# Four_Track_R1.net
KiCad netlist of a schematic drawn in EAGLE
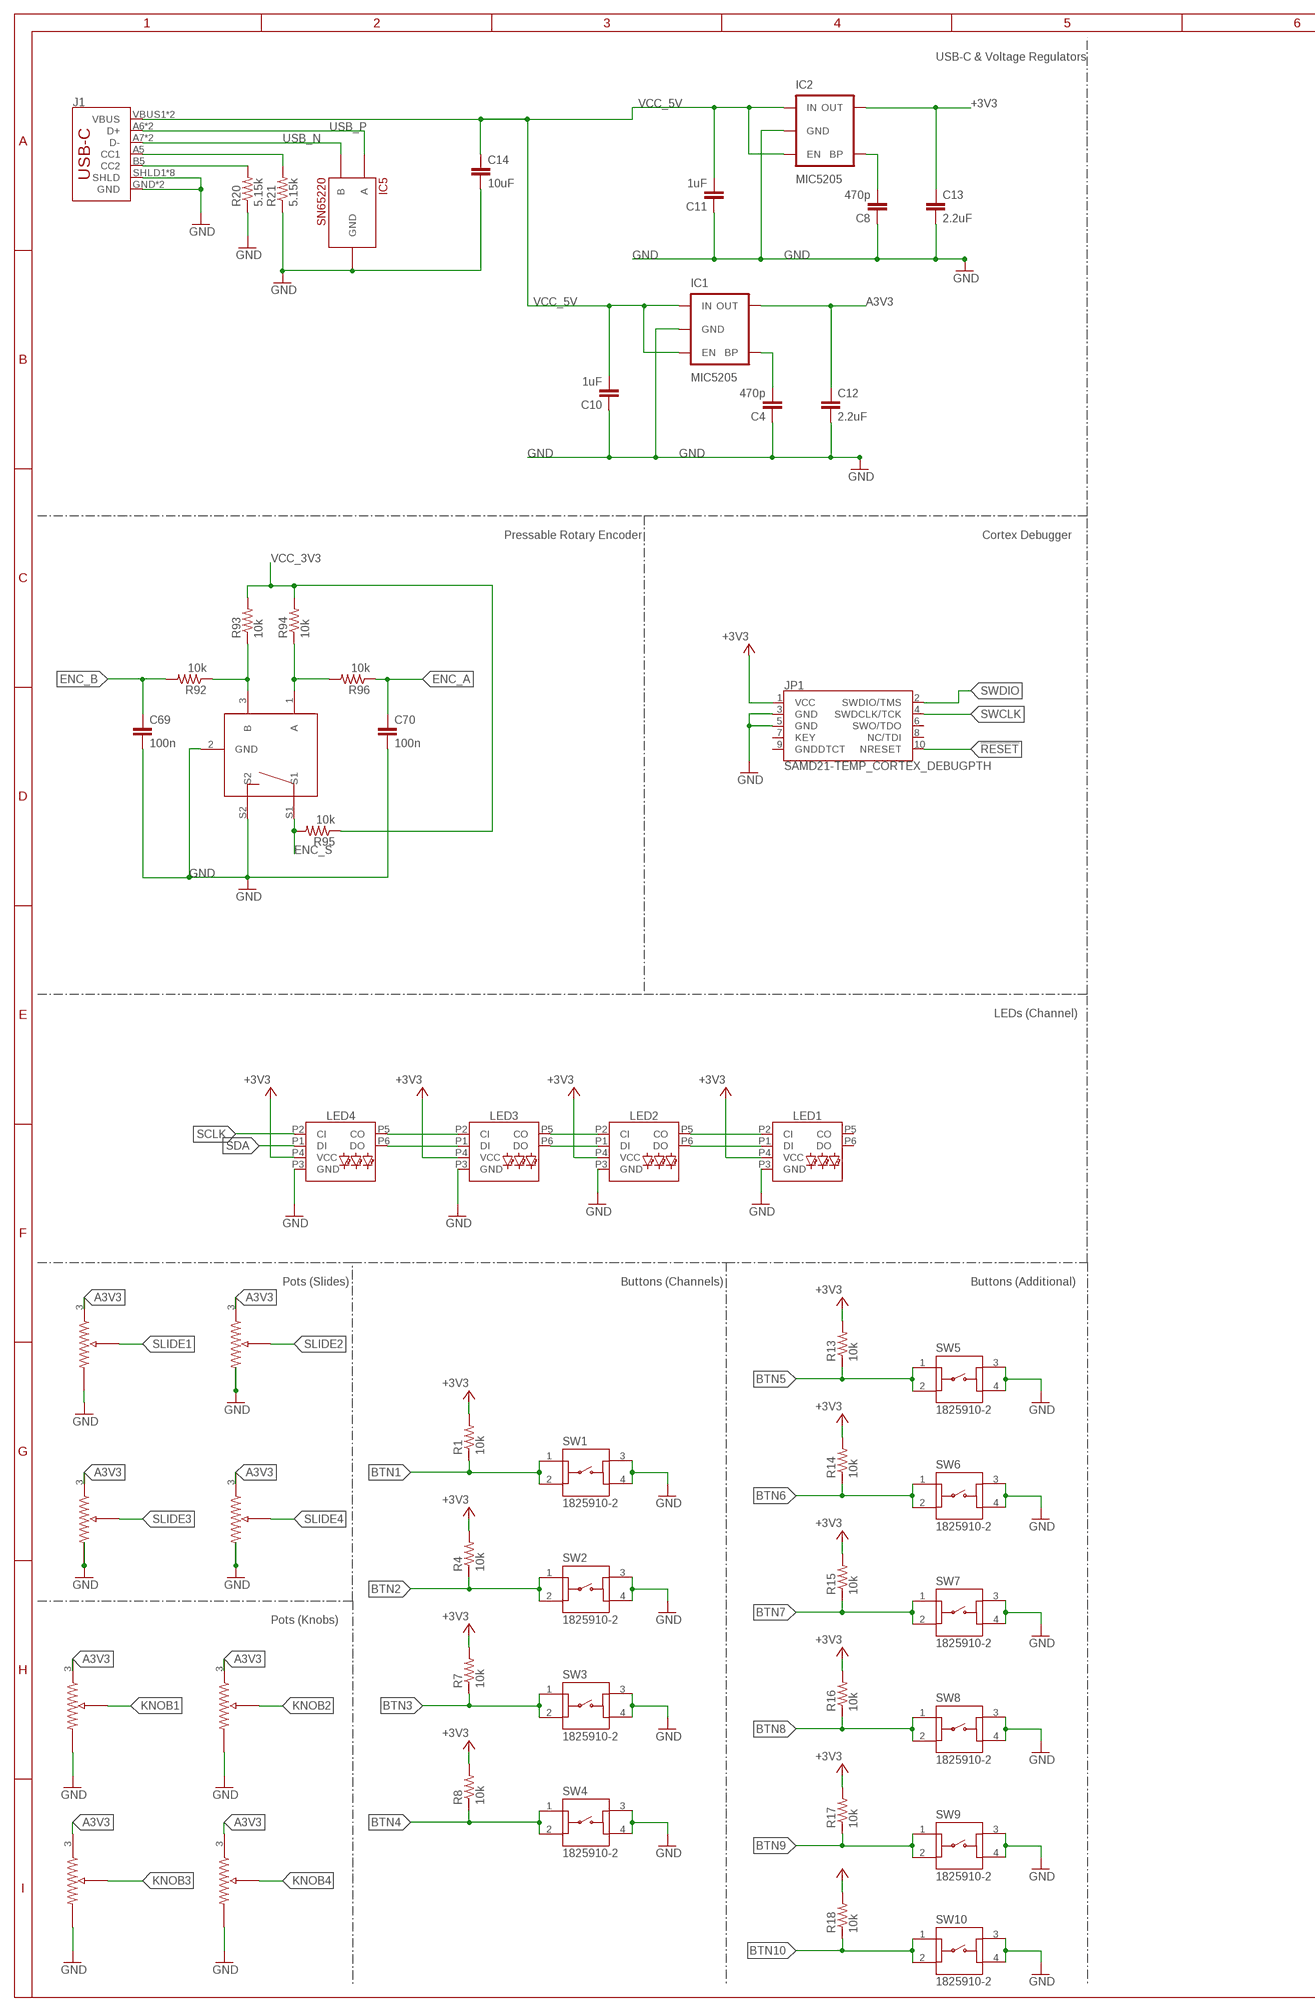
[diagram p0: schematic, sheet 1, part 1 of 2]
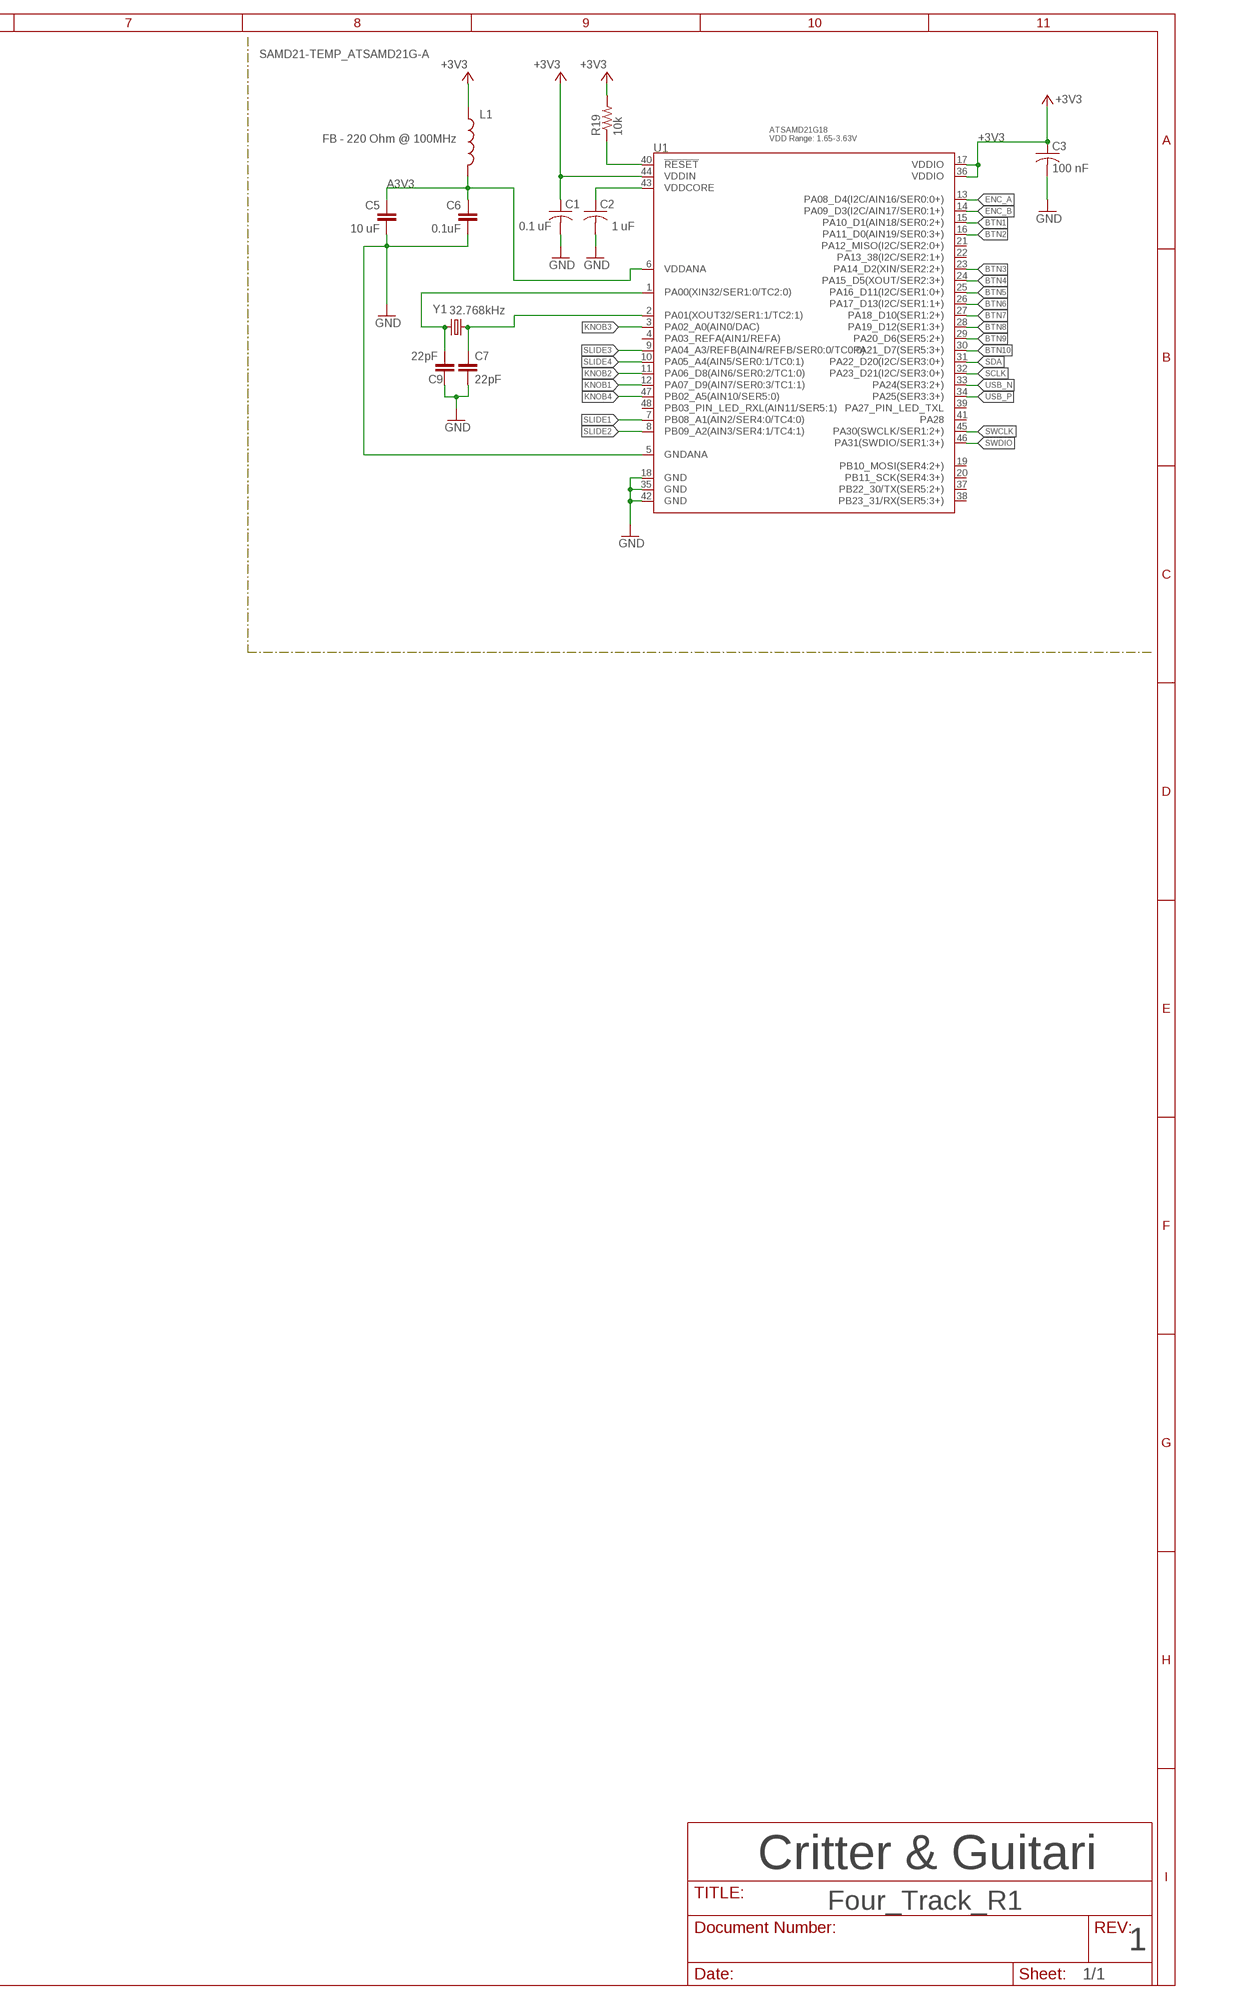
[diagram p1: schematic, sheet 1, part 2 of 2]

(export (version "E")
  (design (tool "Eeschema 10.0.6"))
  (components
    (comp (ref "C1")
      (value "0.1 uF")
      (footprint "eagle-import:C0603")
      (libsource (lib "eagle-import") (part "C-USC0603"))
    )
    (comp (ref "C2")
      (value "1 uF")
      (footprint "eagle-import:C0603")
      (libsource (lib "eagle-import") (part "C-USC0603"))
    )
    (comp (ref "C3")
      (value "100 nF")
      (footprint "eagle-import:C0603")
      (libsource (lib "eagle-import") (part "C-USC0603"))
    )
    (comp (ref "C4")
      (value "470p")
      (footprint "eagle-import:0603-CAP")
      (libsource (lib "eagle-import") (part "CAP0603-CAP"))
    )
    (comp (ref "C5")
      (value "10 uF")
      (footprint "eagle-import:0603-CAP")
      (libsource (lib "eagle-import") (part "0.1UF-25V(+80/-20%)(0603)"))
    )
    (comp (ref "C6")
      (value "0.1uF")
      (footprint "eagle-import:0603-CAP")
      (libsource (lib "eagle-import") (part "0.1UF-25V(+80/-20%)(0603)"))
    )
    (comp (ref "C7")
      (value "22pF")
      (footprint "eagle-import:0603-CAP")
      (libsource (lib "eagle-import") (part "15PF-50V-5%(0603)"))
    )
    (comp (ref "C8")
      (value "470p")
      (footprint "eagle-import:0603-CAP")
      (libsource (lib "eagle-import") (part "CAP0603-CAP"))
    )
    (comp (ref "C9")
      (value "22pF")
      (footprint "eagle-import:0603-CAP")
      (libsource (lib "eagle-import") (part "15PF-50V-5%(0603)"))
    )
    (comp (ref "C10")
      (value "1uF")
      (footprint "eagle-import:0603-CAP")
      (libsource (lib "eagle-import") (part "CAP0603-CAP"))
    )
    (comp (ref "C11")
      (value "1uF")
      (footprint "eagle-import:0603-CAP")
      (libsource (lib "eagle-import") (part "CAP0603-CAP"))
    )
    (comp (ref "C12")
      (value "2.2uF")
      (footprint "eagle-import:C0805")
      (libsource (lib "eagle-import") (part "C-EUC0805"))
    )
    (comp (ref "C13")
      (value "2.2uF")
      (footprint "eagle-import:C0805")
      (libsource (lib "eagle-import") (part "C-EUC0805"))
    )
    (comp (ref "C14")
      (value "10uF")
      (footprint "eagle-import:C1206")
      (libsource (lib "eagle-import") (part "C-EUC1206"))
    )
    (comp (ref "C69")
      (value "100n")
      (footprint "eagle-import:0603-CAP")
      (libsource (lib "eagle-import") (part "CAP0603-CAP"))
    )
    (comp (ref "C70")
      (value "100n")
      (footprint "eagle-import:0603-CAP")
      (libsource (lib "eagle-import") (part "CAP0603-CAP"))
    )
    (comp (ref "IC1")
      (value "MIC5205")
      (footprint "eagle-import:SPARKFUN-3-2-07_SOT23-5")
      (libsource (lib "eagle-import") (part "V_REG_LDOSMD"))
    )
    (comp (ref "IC2")
      (value "MIC5205")
      (footprint "eagle-import:SPARKFUN-3-2-07_SOT23-5")
      (libsource (lib "eagle-import") (part "V_REG_LDOSMD"))
    )
    (comp (ref "IC5")
      (value "SN65220")
      (footprint "eagle-import:SOT23-6L")
      (libsource (lib "eagle-import") (part "SN65220"))
    )
    (comp (ref "J1")
      (value "SPARKFUN-CONNECTORS_USB_C16PIN")
      (footprint "eagle-import:SPARKFUN-CONNECTORS_USB-C-16P")
      (libsource (lib "eagle-import") (part "SPARKFUN-CONNECTORS_USB_C16PIN"))
    )
    (comp (ref "JP1")
      (value "SAMD21-TEMP_CORTEX_DEBUGPTH")
      (footprint "eagle-import:SAMD21-TEMP_2X5-PTH-1.27MM")
      (libsource (lib "eagle-import") (part "SAMD21-TEMP_CORTEX_DEBUGPTH"))
    )
    (comp (ref "L1")
      (value "FB - 220 Ohm @ 100MHz")
      (footprint "eagle-import:0603")
      (libsource (lib "eagle-import") (part "INDUCTOR0603"))
    )
    (comp (ref "LED1")
      (value "SPARKFUN-LED_APA102-5050")
      (footprint "eagle-import:SPARKFUN-LED_APA102-5050")
      (libsource (lib "eagle-import") (part "SPARKFUN-LED_APA102-5050"))
    )
    (comp (ref "LED2")
      (value "SPARKFUN-LED_APA102-5050")
      (footprint "eagle-import:SPARKFUN-LED_APA102-5050")
      (libsource (lib "eagle-import") (part "SPARKFUN-LED_APA102-5050"))
    )
    (comp (ref "LED3")
      (value "SPARKFUN-LED_APA102-5050")
      (footprint "eagle-import:SPARKFUN-LED_APA102-5050")
      (libsource (lib "eagle-import") (part "SPARKFUN-LED_APA102-5050"))
    )
    (comp (ref "LED4")
      (value "SPARKFUN-LED_APA102-5050")
      (footprint "eagle-import:SPARKFUN-LED_APA102-5050")
      (libsource (lib "eagle-import") (part "SPARKFUN-LED_APA102-5050"))
    )
    (comp (ref "R1")
      (value "10k")
      (footprint "eagle-import:R0603")
      (libsource (lib "eagle-import") (part "R-US_R0603"))
    )
    (comp (ref "R2")
      (value "POTPTA45")
      (footprint "eagle-import:SLIDE_POT_PTA4543")
      (libsource (lib "eagle-import") (part "POTPTA45"))
    )
    (comp (ref "R3")
      (value "POTPTA45")
      (footprint "eagle-import:SLIDE_POT_PTA4543")
      (libsource (lib "eagle-import") (part "POTPTA45"))
    )
    (comp (ref "R4")
      (value "10k")
      (footprint "eagle-import:R0603")
      (libsource (lib "eagle-import") (part "R-US_R0603"))
    )
    (comp (ref "R5")
      (value "POTPTA45")
      (footprint "eagle-import:SLIDE_POT_PTA4543")
      (libsource (lib "eagle-import") (part "POTPTA45"))
    )
    (comp (ref "R6")
      (value "POTVERT")
      (footprint "eagle-import:POT-P09X-VERT")
      (libsource (lib "eagle-import") (part "POTVERT"))
    )
    (comp (ref "R7")
      (value "10k")
      (footprint "eagle-import:R0603")
      (libsource (lib "eagle-import") (part "R-US_R0603"))
    )
    (comp (ref "R8")
      (value "10k")
      (footprint "eagle-import:R0603")
      (libsource (lib "eagle-import") (part "R-US_R0603"))
    )
    (comp (ref "R9")
      (value "POTVERT")
      (footprint "eagle-import:POT-P09X-VERT")
      (libsource (lib "eagle-import") (part "POTVERT"))
    )
    (comp (ref "R10")
      (value "POTVERT")
      (footprint "eagle-import:POT-P09X-VERT")
      (libsource (lib "eagle-import") (part "POTVERT"))
    )
    (comp (ref "R11")
      (value "POTPTA45")
      (footprint "eagle-import:SLIDE_POT_PTA4543")
      (libsource (lib "eagle-import") (part "POTPTA45"))
    )
    (comp (ref "R12")
      (value "POTVERT")
      (footprint "eagle-import:POT-P09X-VERT")
      (libsource (lib "eagle-import") (part "POTVERT"))
    )
    (comp (ref "R13")
      (value "10k")
      (footprint "eagle-import:R0603")
      (libsource (lib "eagle-import") (part "R-US_R0603"))
    )
    (comp (ref "R14")
      (value "10k")
      (footprint "eagle-import:R0603")
      (libsource (lib "eagle-import") (part "R-US_R0603"))
    )
    (comp (ref "R15")
      (value "10k")
      (footprint "eagle-import:R0603")
      (libsource (lib "eagle-import") (part "R-US_R0603"))
    )
    (comp (ref "R16")
      (value "10k")
      (footprint "eagle-import:R0603")
      (libsource (lib "eagle-import") (part "R-US_R0603"))
    )
    (comp (ref "R17")
      (value "10k")
      (footprint "eagle-import:R0603")
      (libsource (lib "eagle-import") (part "R-US_R0603"))
    )
    (comp (ref "R18")
      (value "10k")
      (footprint "eagle-import:R0603")
      (libsource (lib "eagle-import") (part "R-US_R0603"))
    )
    (comp (ref "R19")
      (value "10k")
      (footprint "eagle-import:R0603")
      (libsource (lib "eagle-import") (part "R-US_R0603"))
    )
    (comp (ref "R20")
      (value "5.15k")
      (footprint "eagle-import:R0603")
      (libsource (lib "eagle-import") (part "R-US_R0603"))
    )
    (comp (ref "R21")
      (value "5.15k")
      (footprint "eagle-import:R0603")
      (libsource (lib "eagle-import") (part "R-US_R0603"))
    )
    (comp (ref "R92")
      (value "10k")
      (footprint "eagle-import:0603-RES")
      (libsource (lib "eagle-import") (part "RESISTOR0603-RES"))
    )
    (comp (ref "R93")
      (value "10k")
      (footprint "eagle-import:0603-RES")
      (libsource (lib "eagle-import") (part "RESISTOR0603-RES"))
    )
    (comp (ref "R94")
      (value "10k")
      (footprint "eagle-import:0603-RES")
      (libsource (lib "eagle-import") (part "RESISTOR0603-RES"))
    )
    (comp (ref "R95")
      (value "10k")
      (footprint "eagle-import:0603-RES")
      (libsource (lib "eagle-import") (part "RESISTOR0603-RES"))
    )
    (comp (ref "R96")
      (value "10k")
      (footprint "eagle-import:0603-RES")
      (libsource (lib "eagle-import") (part "RESISTOR0603-RES"))
    )
    (comp (ref "S3")
      (value "ENCODER_SWITCH")
      (footprint "eagle-import:ENCODER_SWITCH")
      (fields (field (name "SPICEPREFIX") "X"))
      (libsource (lib "eagle-import") (part "ENCODER_SWITCH"))
    )
    (comp (ref "SW1")
      (value "1825910-2")
      (footprint "eagle-import:TE_1825910-2")
      (fields (field (name "MF") "TE Connectivity"))
      (libsource (lib "eagle-import") (part "1825910-2"))
    )
    (comp (ref "SW2")
      (value "1825910-2")
      (footprint "eagle-import:TE_1825910-2")
      (fields (field (name "MF") "TE Connectivity"))
      (libsource (lib "eagle-import") (part "1825910-2"))
    )
    (comp (ref "SW3")
      (value "1825910-2")
      (footprint "eagle-import:TE_1825910-2")
      (fields (field (name "MF") "TE Connectivity"))
      (libsource (lib "eagle-import") (part "1825910-2"))
    )
    (comp (ref "SW4")
      (value "1825910-2")
      (footprint "eagle-import:TE_1825910-2")
      (fields (field (name "MF") "TE Connectivity"))
      (libsource (lib "eagle-import") (part "1825910-2"))
    )
    (comp (ref "SW5")
      (value "1825910-2")
      (footprint "eagle-import:TE_1825910-2")
      (fields (field (name "MF") "TE Connectivity"))
      (libsource (lib "eagle-import") (part "1825910-2"))
    )
    (comp (ref "SW6")
      (value "1825910-2")
      (footprint "eagle-import:TE_1825910-2")
      (fields (field (name "MF") "TE Connectivity"))
      (libsource (lib "eagle-import") (part "1825910-2"))
    )
    (comp (ref "SW7")
      (value "1825910-2")
      (footprint "eagle-import:TE_1825910-2")
      (fields (field (name "MF") "TE Connectivity"))
      (libsource (lib "eagle-import") (part "1825910-2"))
    )
    (comp (ref "SW8")
      (value "1825910-2")
      (footprint "eagle-import:TE_1825910-2")
      (fields (field (name "MF") "TE Connectivity"))
      (libsource (lib "eagle-import") (part "1825910-2"))
    )
    (comp (ref "SW9")
      (value "1825910-2")
      (footprint "eagle-import:TE_1825910-2")
      (fields (field (name "MF") "TE Connectivity"))
      (libsource (lib "eagle-import") (part "1825910-2"))
    )
    (comp (ref "SW10")
      (value "1825910-2")
      (footprint "eagle-import:TE_1825910-2")
      (fields (field (name "MF") "TE Connectivity"))
      (libsource (lib "eagle-import") (part "1825910-2"))
    )
    (comp (ref "U1")
      (value "SAMD21-TEMP_ATSAMD21G-A")
      (footprint "eagle-import:SAMD21-TEMP_TQFP-48")
      (fields (field (name "CID") "448"))
      (libsource (lib "eagle-import") (part "SAMD21-TEMP_ATSAMD21G-A"))
    )
    (comp (ref "Y1")
      (value "32.768kHz")
      (footprint "eagle-import:CRYSTAL-SMD-3.2X1.5MM")
      (libsource (lib "eagle-import") (part "CRYSTAL3.2X1.5MM"))
    )
  )
  (nets
    (net (code "1") (name "+3V3") (class "Default")
      (node (ref "C1") (pin "1") (pinfunction "1_1") (pintype "passive"))
      (node (ref "C13") (pin "1") (pinfunction "1_1") (pintype "passive"))
      (node (ref "C3") (pin "1") (pinfunction "1_1") (pintype "passive"))
      (node (ref "IC2") (pin "5") (pinfunction "OUT_5") (pintype "passive"))
      (node (ref "JP1") (pin "1") (pinfunction "VCC_1") (pintype "bidirectional"))
      (node (ref "L1") (pin "1") (pinfunction "1_1") (pintype "passive"))
      (node (ref "LED1") (pin "P4") (pinfunction "VCC_P4") (pintype "bidirectional"))
      (node (ref "LED2") (pin "P4") (pinfunction "VCC_P4") (pintype "bidirectional"))
      (node (ref "LED3") (pin "P4") (pinfunction "VCC_P4") (pintype "bidirectional"))
      (node (ref "LED4") (pin "P4") (pinfunction "VCC_P4") (pintype "bidirectional"))
      (node (ref "R1") (pin "2") (pinfunction "2_2") (pintype "passive"))
      (node (ref "R13") (pin "2") (pinfunction "2_2") (pintype "passive"))
      (node (ref "R14") (pin "2") (pinfunction "2_2") (pintype "passive"))
      (node (ref "R15") (pin "2") (pinfunction "2_2") (pintype "passive"))
      (node (ref "R16") (pin "2") (pinfunction "2_2") (pintype "passive"))
      (node (ref "R17") (pin "2") (pinfunction "2_2") (pintype "passive"))
      (node (ref "R18") (pin "2") (pinfunction "2_2") (pintype "passive"))
      (node (ref "R19") (pin "2") (pinfunction "2_2") (pintype "passive"))
      (node (ref "R4") (pin "2") (pinfunction "2_2") (pintype "passive"))
      (node (ref "R7") (pin "2") (pinfunction "2_2") (pintype "passive"))
      (node (ref "R8") (pin "2") (pinfunction "2_2") (pintype "passive"))
      (node (ref "U1") (pin "17") (pinfunction "VDDIO_17") (pintype "bidirectional"))
      (node (ref "U1") (pin "36") (pinfunction "VDDIO_36") (pintype "bidirectional"))
      (node (ref "U1") (pin "44") (pinfunction "VDDIN_44") (pintype "bidirectional"))
    )
    (net (code "2") (name "/ENC_S") (class "Default")
      (node (ref "R95") (pin "2") (pinfunction "2_2") (pintype "passive"))
      (node (ref "S3") (pin "S1") (pinfunction "S1_S1") (pintype "bidirectional"))
    )
    (net (code "3") (name "/VCC_3V3") (class "Default")
      (node (ref "R93") (pin "2") (pinfunction "2_2") (pintype "passive"))
      (node (ref "R94") (pin "2") (pinfunction "2_2") (pintype "passive"))
      (node (ref "R95") (pin "1") (pinfunction "1_1") (pintype "passive"))
    )
    (net (code "4") (name "/VCC_5V") (class "Default")
      (node (ref "C10") (pin "2") (pinfunction "2_2") (pintype "passive"))
      (node (ref "C11") (pin "2") (pinfunction "2_2") (pintype "passive"))
      (node (ref "C14") (pin "1") (pinfunction "1_1") (pintype "passive"))
      (node (ref "IC1") (pin "1") (pinfunction "IN_1") (pintype "input"))
      (node (ref "IC1") (pin "3") (pinfunction "EN_3") (pintype "input"))
      (node (ref "IC2") (pin "1") (pinfunction "IN_1") (pintype "input"))
      (node (ref "IC2") (pin "3") (pinfunction "EN_3") (pintype "input"))
      (node (ref "J1") (pin "VBUS1") (pinfunction "VBUS_VBUS1") (pintype "bidirectional"))
      (node (ref "J1") (pin "VBUS2") (pinfunction "VBUS_VBUS2") (pintype "bidirectional"))
    )
    (net (code "5") (name "/~{RESET}") (class "Default")
      (node (ref "JP1") (pin "10") (pinfunction "NRESET_10") (pintype "bidirectional"))
      (node (ref "R19") (pin "1") (pinfunction "1_1") (pintype "passive"))
      (node (ref "U1") (pin "40") (pinfunction "~{RESET}_40") (pintype "bidirectional"))
    )
    (net (code "6") (name "A3V3") (class "Default")
      (node (ref "C12") (pin "1") (pinfunction "1_1") (pintype "passive"))
      (node (ref "C5") (pin "1") (pinfunction "1_1") (pintype "passive"))
      (node (ref "C6") (pin "1") (pinfunction "1_1") (pintype "passive"))
      (node (ref "IC1") (pin "5") (pinfunction "OUT_5") (pintype "passive"))
      (node (ref "L1") (pin "2") (pinfunction "2_2") (pintype "passive"))
      (node (ref "R10") (pin "3") (pinfunction "P$3_3") (pintype "bidirectional"))
      (node (ref "R11") (pin "3") (pinfunction "P$3_3") (pintype "bidirectional"))
      (node (ref "R12") (pin "3") (pinfunction "P$3_3") (pintype "bidirectional"))
      (node (ref "R2") (pin "3") (pinfunction "P$3_3") (pintype "bidirectional"))
      (node (ref "R3") (pin "3") (pinfunction "P$3_3") (pintype "bidirectional"))
      (node (ref "R5") (pin "3") (pinfunction "P$3_3") (pintype "bidirectional"))
      (node (ref "R6") (pin "3") (pinfunction "P$3_3") (pintype "bidirectional"))
      (node (ref "R9") (pin "3") (pinfunction "P$3_3") (pintype "bidirectional"))
      (node (ref "U1") (pin "6") (pinfunction "VDDANA_6") (pintype "bidirectional"))
    )
    (net (code "7") (name "BTN1") (class "Default")
      (node (ref "R1") (pin "1") (pinfunction "1_1") (pintype "passive"))
      (node (ref "SW1") (pin "1") (pinfunction "1_1") (pintype "passive"))
      (node (ref "SW1") (pin "2") (pinfunction "2_2") (pintype "passive"))
      (node (ref "U1") (pin "15") (pinfunction "PA10_D1(AIN18/SER0:2+)_15") (pintype "bidirectional"))
    )
    (net (code "8") (name "BTN2") (class "Default")
      (node (ref "R4") (pin "1") (pinfunction "1_1") (pintype "passive"))
      (node (ref "SW2") (pin "1") (pinfunction "1_1") (pintype "passive"))
      (node (ref "SW2") (pin "2") (pinfunction "2_2") (pintype "passive"))
      (node (ref "U1") (pin "16") (pinfunction "PA11_D0(AIN19/SER0:3+)_16") (pintype "bidirectional"))
    )
    (net (code "9") (name "BTN3") (class "Default")
      (node (ref "R7") (pin "1") (pinfunction "1_1") (pintype "passive"))
      (node (ref "SW3") (pin "1") (pinfunction "1_1") (pintype "passive"))
      (node (ref "SW3") (pin "2") (pinfunction "2_2") (pintype "passive"))
      (node (ref "U1") (pin "23") (pinfunction "PA14_D2(XIN/SER2:2+)_23") (pintype "bidirectional"))
    )
    (net (code "10") (name "BTN4") (class "Default")
      (node (ref "R8") (pin "1") (pinfunction "1_1") (pintype "passive"))
      (node (ref "SW4") (pin "1") (pinfunction "1_1") (pintype "passive"))
      (node (ref "SW4") (pin "2") (pinfunction "2_2") (pintype "passive"))
      (node (ref "U1") (pin "24") (pinfunction "PA15_D5(XOUT/SER2:3+)_24") (pintype "bidirectional"))
    )
    (net (code "11") (name "BTN5") (class "Default")
      (node (ref "R13") (pin "1") (pinfunction "1_1") (pintype "passive"))
      (node (ref "SW5") (pin "1") (pinfunction "1_1") (pintype "passive"))
      (node (ref "SW5") (pin "2") (pinfunction "2_2") (pintype "passive"))
      (node (ref "U1") (pin "25") (pinfunction "PA16_D11(I2C/SER1:0+)_25") (pintype "bidirectional"))
    )
    (net (code "12") (name "BTN6") (class "Default")
      (node (ref "R14") (pin "1") (pinfunction "1_1") (pintype "passive"))
      (node (ref "SW6") (pin "1") (pinfunction "1_1") (pintype "passive"))
      (node (ref "SW6") (pin "2") (pinfunction "2_2") (pintype "passive"))
      (node (ref "U1") (pin "26") (pinfunction "PA17_D13(I2C/SER1:1+)_26") (pintype "bidirectional"))
    )
    (net (code "13") (name "BTN7") (class "Default")
      (node (ref "R15") (pin "1") (pinfunction "1_1") (pintype "passive"))
      (node (ref "SW7") (pin "1") (pinfunction "1_1") (pintype "passive"))
      (node (ref "SW7") (pin "2") (pinfunction "2_2") (pintype "passive"))
      (node (ref "U1") (pin "27") (pinfunction "PA18_D10(SER1:2+)_27") (pintype "bidirectional"))
    )
    (net (code "14") (name "BTN8") (class "Default")
      (node (ref "R16") (pin "1") (pinfunction "1_1") (pintype "passive"))
      (node (ref "SW8") (pin "1") (pinfunction "1_1") (pintype "passive"))
      (node (ref "SW8") (pin "2") (pinfunction "2_2") (pintype "passive"))
      (node (ref "U1") (pin "28") (pinfunction "PA19_D12(SER1:3+)_28") (pintype "bidirectional"))
    )
    (net (code "15") (name "BTN9") (class "Default")
      (node (ref "R17") (pin "1") (pinfunction "1_1") (pintype "passive"))
      (node (ref "SW9") (pin "1") (pinfunction "1_1") (pintype "passive"))
      (node (ref "SW9") (pin "2") (pinfunction "2_2") (pintype "passive"))
      (node (ref "U1") (pin "29") (pinfunction "PA20_D6(SER5:2+)_29") (pintype "bidirectional"))
    )
    (net (code "16") (name "BTN10") (class "Default")
      (node (ref "R18") (pin "1") (pinfunction "1_1") (pintype "passive"))
      (node (ref "SW10") (pin "1") (pinfunction "1_1") (pintype "passive"))
      (node (ref "SW10") (pin "2") (pinfunction "2_2") (pintype "passive"))
      (node (ref "U1") (pin "30") (pinfunction "PA21_D7(SER5:3+)_30") (pintype "bidirectional"))
    )
    (net (code "17") (name "ENC_A") (class "Default")
      (node (ref "C70") (pin "1") (pinfunction "1_1") (pintype "passive"))
      (node (ref "R96") (pin "1") (pinfunction "1_1") (pintype "passive"))
      (node (ref "U1") (pin "13") (pinfunction "PA08_D4(I2C/AIN16/SER0:0+)_13") (pintype "bidirectional"))
    )
    (net (code "18") (name "ENC_B") (class "Default")
      (node (ref "C69") (pin "1") (pinfunction "1_1") (pintype "passive"))
      (node (ref "R92") (pin "2") (pinfunction "2_2") (pintype "passive"))
      (node (ref "U1") (pin "14") (pinfunction "PA09_D3(I2C/AIN17/SER0:1+)_14") (pintype "bidirectional"))
    )
    (net (code "19") (name "GND") (class "Default")
      (node (ref "C1") (pin "2") (pinfunction "2_2") (pintype "passive"))
      (node (ref "C10") (pin "1") (pinfunction "1_1") (pintype "passive"))
      (node (ref "C11") (pin "1") (pinfunction "1_1") (pintype "passive"))
      (node (ref "C12") (pin "2") (pinfunction "2_2") (pintype "passive"))
      (node (ref "C13") (pin "2") (pinfunction "2_2") (pintype "passive"))
      (node (ref "C14") (pin "2") (pinfunction "2_2") (pintype "passive"))
      (node (ref "C2") (pin "2") (pinfunction "2_2") (pintype "passive"))
      (node (ref "C3") (pin "2") (pinfunction "2_2") (pintype "passive"))
      (node (ref "C4") (pin "1") (pinfunction "1_1") (pintype "passive"))
      (node (ref "C5") (pin "2") (pinfunction "2_2") (pintype "passive"))
      (node (ref "C6") (pin "2") (pinfunction "2_2") (pintype "passive"))
      (node (ref "C69") (pin "2") (pinfunction "2_2") (pintype "passive"))
      (node (ref "C7") (pin "2") (pinfunction "2_2") (pintype "passive"))
      (node (ref "C70") (pin "2") (pinfunction "2_2") (pintype "passive"))
      (node (ref "C8") (pin "1") (pinfunction "1_1") (pintype "passive"))
      (node (ref "C9") (pin "1") (pinfunction "1_1") (pintype "passive"))
      (node (ref "IC1") (pin "2") (pinfunction "GND_2") (pintype "input"))
      (node (ref "IC2") (pin "2") (pinfunction "GND_2") (pintype "input"))
      (node (ref "IC5") (pin "2") (pinfunction "GND_2") (pintype "bidirectional"))
      (node (ref "IC5") (pin "5") (pinfunction "GND_5") (pintype "bidirectional"))
      (node (ref "J1") (pin "GND") (pinfunction "GND_GND") (pintype "bidirectional"))
      (node (ref "J1") (pin "GND2") (pinfunction "GND_GND2") (pintype "bidirectional"))
      (node (ref "J1") (pin "SHLD1") (pinfunction "SHLD_SHLD1") (pintype "bidirectional"))
      (node (ref "J1") (pin "SHLD2") (pinfunction "SHLD_SHLD2") (pintype "bidirectional"))
      (node (ref "J1") (pin "SHLD3") (pinfunction "SHLD_SHLD3") (pintype "bidirectional"))
      (node (ref "J1") (pin "SHLD4") (pinfunction "SHLD_SHLD4") (pintype "bidirectional"))
      (node (ref "J1") (pin "SHLD5") (pinfunction "SHLD_SHLD5") (pintype "bidirectional"))
      (node (ref "J1") (pin "SHLD6") (pinfunction "SHLD_SHLD6") (pintype "bidirectional"))
      (node (ref "J1") (pin "SHLD7") (pinfunction "SHLD_SHLD7") (pintype "bidirectional"))
      (node (ref "J1") (pin "SHLD8") (pinfunction "SHLD_SHLD8") (pintype "bidirectional"))
      (node (ref "JP1") (pin "3") (pinfunction "GND_3") (pintype "bidirectional"))
      (node (ref "JP1") (pin "5") (pinfunction "GND_5") (pintype "bidirectional"))
      (node (ref "LED1") (pin "P3") (pinfunction "GND_P3") (pintype "bidirectional"))
      (node (ref "LED2") (pin "P3") (pinfunction "GND_P3") (pintype "bidirectional"))
      (node (ref "LED3") (pin "P3") (pinfunction "GND_P3") (pintype "bidirectional"))
      (node (ref "LED4") (pin "P3") (pinfunction "GND_P3") (pintype "bidirectional"))
      (node (ref "R10") (pin "1") (pinfunction "P$2_1") (pintype "bidirectional"))
      (node (ref "R11") (pin "1") (pinfunction "P$2_1") (pintype "bidirectional"))
      (node (ref "R12") (pin "1") (pinfunction "P$2_1") (pintype "bidirectional"))
      (node (ref "R2") (pin "1") (pinfunction "P$2_1") (pintype "bidirectional"))
      (node (ref "R20") (pin "1") (pinfunction "1_1") (pintype "passive"))
      (node (ref "R21") (pin "1") (pinfunction "1_1") (pintype "passive"))
      (node (ref "R3") (pin "1") (pinfunction "P$2_1") (pintype "bidirectional"))
      (node (ref "R5") (pin "1") (pinfunction "P$2_1") (pintype "bidirectional"))
      (node (ref "R6") (pin "1") (pinfunction "P$2_1") (pintype "bidirectional"))
      (node (ref "R9") (pin "1") (pinfunction "P$2_1") (pintype "bidirectional"))
      (node (ref "S3") (pin "2") (pinfunction "GND_2") (pintype "bidirectional"))
      (node (ref "S3") (pin "S2") (pinfunction "S2_S2") (pintype "bidirectional"))
      (node (ref "SW1") (pin "3") (pinfunction "3_3") (pintype "passive"))
      (node (ref "SW1") (pin "4") (pinfunction "4_4") (pintype "passive"))
      (node (ref "SW10") (pin "3") (pinfunction "3_3") (pintype "passive"))
      (node (ref "SW10") (pin "4") (pinfunction "4_4") (pintype "passive"))
      (node (ref "SW2") (pin "3") (pinfunction "3_3") (pintype "passive"))
      (node (ref "SW2") (pin "4") (pinfunction "4_4") (pintype "passive"))
      (node (ref "SW3") (pin "3") (pinfunction "3_3") (pintype "passive"))
      (node (ref "SW3") (pin "4") (pinfunction "4_4") (pintype "passive"))
      (node (ref "SW4") (pin "3") (pinfunction "3_3") (pintype "passive"))
      (node (ref "SW4") (pin "4") (pinfunction "4_4") (pintype "passive"))
      (node (ref "SW5") (pin "3") (pinfunction "3_3") (pintype "passive"))
      (node (ref "SW5") (pin "4") (pinfunction "4_4") (pintype "passive"))
      (node (ref "SW6") (pin "3") (pinfunction "3_3") (pintype "passive"))
      (node (ref "SW6") (pin "4") (pinfunction "4_4") (pintype "passive"))
      (node (ref "SW7") (pin "3") (pinfunction "3_3") (pintype "passive"))
      (node (ref "SW7") (pin "4") (pinfunction "4_4") (pintype "passive"))
      (node (ref "SW8") (pin "3") (pinfunction "3_3") (pintype "passive"))
      (node (ref "SW8") (pin "4") (pinfunction "4_4") (pintype "passive"))
      (node (ref "SW9") (pin "3") (pinfunction "3_3") (pintype "passive"))
      (node (ref "SW9") (pin "4") (pinfunction "4_4") (pintype "passive"))
      (node (ref "U1") (pin "18") (pinfunction "GND_18") (pintype "bidirectional"))
      (node (ref "U1") (pin "35") (pinfunction "GND_35") (pintype "bidirectional"))
      (node (ref "U1") (pin "42") (pinfunction "GND_42") (pintype "bidirectional"))
      (node (ref "U1") (pin "5") (pinfunction "GNDANA_5") (pintype "bidirectional"))
    )
    (net (code "20") (name "KNOB1") (class "Default")
      (node (ref "R6") (pin "WIPER") (pinfunction "P$1_WIPER") (pintype "bidirectional"))
      (node (ref "U1") (pin "12") (pinfunction "PA07_D9(AIN7/SER0:3/TC1:1)_12") (pintype "bidirectional"))
    )
    (net (code "21") (name "KNOB2") (class "Default")
      (node (ref "R12") (pin "WIPER") (pinfunction "P$1_WIPER") (pintype "bidirectional"))
      (node (ref "U1") (pin "11") (pinfunction "PA06_D8(AIN6/SER0:2/TC1:0)_11") (pintype "bidirectional"))
    )
    (net (code "22") (name "KNOB3") (class "Default")
      (node (ref "R9") (pin "WIPER") (pinfunction "P$1_WIPER") (pintype "bidirectional"))
      (node (ref "U1") (pin "3") (pinfunction "PA02_A0(AIN0/DAC)_3") (pintype "bidirectional"))
    )
    (net (code "23") (name "KNOB4") (class "Default")
      (node (ref "R10") (pin "WIPER") (pinfunction "P$1_WIPER") (pintype "bidirectional"))
      (node (ref "U1") (pin "47") (pinfunction "PB02_A5(AIN10/SER5:0)_47") (pintype "bidirectional"))
    )
    (net (code "24") (name "Net-(IC1-BP)") (class "Default")
      (node (ref "C4") (pin "2") (pinfunction "2_2") (pintype "passive"))
      (node (ref "IC1") (pin "4") (pinfunction "BP_4") (pintype "input"))
    )
    (net (code "25") (name "Net-(IC2-BP)") (class "Default")
      (node (ref "C8") (pin "2") (pinfunction "2_2") (pintype "passive"))
      (node (ref "IC2") (pin "4") (pinfunction "BP_4") (pintype "input"))
    )
    (net (code "26") (name "Net-(J1-CC1)") (class "Default")
      (node (ref "J1") (pin "A5") (pinfunction "CC1_A5") (pintype "bidirectional"))
      (node (ref "R21") (pin "2") (pinfunction "2_2") (pintype "passive"))
    )
    (net (code "27") (name "Net-(J1-CC2)") (class "Default")
      (node (ref "J1") (pin "B5") (pinfunction "CC2_B5") (pintype "bidirectional"))
      (node (ref "R20") (pin "2") (pinfunction "2_2") (pintype "passive"))
    )
    (net (code "28") (name "Net-(LED1-CI)") (class "Default")
      (node (ref "LED1") (pin "P2") (pinfunction "CI_P2") (pintype "bidirectional"))
      (node (ref "LED2") (pin "P5") (pinfunction "CO_P5") (pintype "bidirectional"))
    )
    (net (code "29") (name "Net-(LED1-DI)") (class "Default")
      (node (ref "LED1") (pin "P1") (pinfunction "DI_P1") (pintype "bidirectional"))
      (node (ref "LED2") (pin "P6") (pinfunction "DO_P6") (pintype "bidirectional"))
    )
    (net (code "30") (name "Net-(LED2-CI)") (class "Default")
      (node (ref "LED2") (pin "P2") (pinfunction "CI_P2") (pintype "bidirectional"))
      (node (ref "LED3") (pin "P5") (pinfunction "CO_P5") (pintype "bidirectional"))
    )
    (net (code "31") (name "Net-(LED2-DI)") (class "Default")
      (node (ref "LED2") (pin "P1") (pinfunction "DI_P1") (pintype "bidirectional"))
      (node (ref "LED3") (pin "P6") (pinfunction "DO_P6") (pintype "bidirectional"))
    )
    (net (code "32") (name "Net-(LED3-CI)") (class "Default")
      (node (ref "LED3") (pin "P2") (pinfunction "CI_P2") (pintype "bidirectional"))
      (node (ref "LED4") (pin "P5") (pinfunction "CO_P5") (pintype "bidirectional"))
    )
    (net (code "33") (name "Net-(LED3-DI)") (class "Default")
      (node (ref "LED3") (pin "P1") (pinfunction "DI_P1") (pintype "bidirectional"))
      (node (ref "LED4") (pin "P6") (pinfunction "DO_P6") (pintype "bidirectional"))
    )
    (net (code "34") (name "Net-(S3-A)") (class "Default")
      (node (ref "R94") (pin "1") (pinfunction "1_1") (pintype "passive"))
      (node (ref "R96") (pin "2") (pinfunction "2_2") (pintype "passive"))
      (node (ref "S3") (pin "1") (pinfunction "A_1") (pintype "bidirectional"))
    )
    (net (code "35") (name "Net-(S3-B)") (class "Default")
      (node (ref "R92") (pin "1") (pinfunction "1_1") (pintype "passive"))
      (node (ref "R93") (pin "1") (pinfunction "1_1") (pintype "passive"))
      (node (ref "S3") (pin "3") (pinfunction "B_3") (pintype "bidirectional"))
    )
    (net (code "36") (name "Net-(U1-PA00(XIN32{slash}SER1:0{slash}TC2:0))") (class "Default")
      (node (ref "C9") (pin "2") (pinfunction "2_2") (pintype "passive"))
      (node (ref "U1") (pin "1") (pinfunction "PA00(XIN32/SER1:0/TC2:0)_1") (pintype "bidirectional"))
      (node (ref "Y1") (pin "P$2") (pinfunction "2_P$2") (pintype "passive"))
    )
    (net (code "37") (name "Net-(U1-PA01(XOUT32{slash}SER1:1{slash}TC2:1))") (class "Default")
      (node (ref "C7") (pin "1") (pinfunction "1_1") (pintype "passive"))
      (node (ref "U1") (pin "2") (pinfunction "PA01(XOUT32/SER1:1/TC2:1)_2") (pintype "bidirectional"))
      (node (ref "Y1") (pin "P$1") (pinfunction "1_P$1") (pintype "passive"))
    )
    (net (code "38") (name "Net-(U1-VDDCORE)") (class "Default")
      (node (ref "C2") (pin "1") (pinfunction "1_1") (pintype "passive"))
      (node (ref "U1") (pin "43") (pinfunction "VDDCORE_43") (pintype "bidirectional"))
    )
    (net (code "39") (name "SCLK") (class "Default")
      (node (ref "LED4") (pin "P2") (pinfunction "CI_P2") (pintype "bidirectional"))
      (node (ref "U1") (pin "32") (pinfunction "PA23_D21(I2C/SER3:0+)_32") (pintype "bidirectional"))
    )
    (net (code "40") (name "SDA") (class "Default")
      (node (ref "LED4") (pin "P1") (pinfunction "DI_P1") (pintype "bidirectional"))
      (node (ref "U1") (pin "31") (pinfunction "PA22_D20(I2C/SER3:0+)_31") (pintype "bidirectional"))
    )
    (net (code "41") (name "SLIDE1") (class "Default")
      (node (ref "R11") (pin "2") (pinfunction "P$1_2") (pintype "bidirectional"))
      (node (ref "U1") (pin "7") (pinfunction "PB08_A1(AIN2/SER4:0/TC4:0)_7") (pintype "bidirectional"))
    )
    (net (code "42") (name "SLIDE2") (class "Default")
      (node (ref "R5") (pin "2") (pinfunction "P$1_2") (pintype "bidirectional"))
      (node (ref "U1") (pin "8") (pinfunction "PB09_A2(AIN3/SER4:1/TC4:1)_8") (pintype "bidirectional"))
    )
    (net (code "43") (name "SLIDE3") (class "Default")
      (node (ref "R2") (pin "2") (pinfunction "P$1_2") (pintype "bidirectional"))
      (node (ref "U1") (pin "9") (pinfunction "PA04_A3/REFB(AIN4/REFB/SER0:0/TC0:0)_9") (pintype "bidirectional"))
    )
    (net (code "44") (name "SLIDE4") (class "Default")
      (node (ref "R3") (pin "2") (pinfunction "P$1_2") (pintype "bidirectional"))
      (node (ref "U1") (pin "10") (pinfunction "PA05_A4(AIN5/SER0:1/TC0:1)_10") (pintype "bidirectional"))
    )
    (net (code "45") (name "SWCLK") (class "Default")
      (node (ref "JP1") (pin "4") (pinfunction "SWDCLK/TCK_4") (pintype "bidirectional"))
      (node (ref "U1") (pin "45") (pinfunction "PA30(SWCLK/SER1:2+)_45") (pintype "bidirectional"))
    )
    (net (code "46") (name "SWDIO") (class "Default")
      (node (ref "JP1") (pin "2") (pinfunction "SWDIO/TMS_2") (pintype "bidirectional"))
      (node (ref "U1") (pin "46") (pinfunction "PA31(SWDIO/SER1:3+)_46") (pintype "bidirectional"))
    )
    (net (code "47") (name "USB_N") (class "Default")
      (node (ref "IC5") (pin "4") (pinfunction "B_4") (pintype "bidirectional"))
      (node (ref "J1") (pin "A7") (pinfunction "D-_A7") (pintype "bidirectional"))
      (node (ref "J1") (pin "B7") (pinfunction "D-_B7") (pintype "bidirectional"))
      (node (ref "U1") (pin "33") (pinfunction "PA24(SER3:2+)_33") (pintype "bidirectional"))
    )
    (net (code "48") (name "USB_P") (class "Default")
      (node (ref "IC5") (pin "6") (pinfunction "A_6") (pintype "bidirectional"))
      (node (ref "J1") (pin "A6") (pinfunction "D+_A6") (pintype "bidirectional"))
      (node (ref "J1") (pin "B6") (pinfunction "D+_B6") (pintype "bidirectional"))
      (node (ref "U1") (pin "34") (pinfunction "PA25(SER3:3+)_34") (pintype "bidirectional"))
    )
    (net (code "49") (name "unconnected-(JP1-GNDDTCT-Pad9)") (class "Default")
      (node (ref "JP1") (pin "9") (pinfunction "GNDDTCT_9") (pintype "bidirectional"))
    )
    (net (code "50") (name "unconnected-(JP1-KEY-Pad7)") (class "Default")
      (node (ref "JP1") (pin "7") (pinfunction "KEY_7") (pintype "bidirectional"))
    )
    (net (code "51") (name "unconnected-(JP1-NC{slash}TDI-Pad8)") (class "Default")
      (node (ref "JP1") (pin "8") (pinfunction "NC/TDI_8") (pintype "bidirectional"))
    )
    (net (code "52") (name "unconnected-(JP1-SWO{slash}TDO-Pad6)") (class "Default")
      (node (ref "JP1") (pin "6") (pinfunction "SWO/TDO_6") (pintype "bidirectional"))
    )
    (net (code "53") (name "unconnected-(LED1-CO-PadP5)") (class "Default")
      (node (ref "LED1") (pin "P5") (pinfunction "CO_P5") (pintype "bidirectional"))
    )
    (net (code "54") (name "unconnected-(LED1-DO-PadP6)") (class "Default")
      (node (ref "LED1") (pin "P6") (pinfunction "DO_P6") (pintype "bidirectional"))
    )
    (net (code "55") (name "unconnected-(U1-PA03_REFA(AIN1{slash}REFA)-Pad4)") (class "Default")
      (node (ref "U1") (pin "4") (pinfunction "PA03_REFA(AIN1/REFA)_4") (pintype "bidirectional"))
    )
    (net (code "56") (name "unconnected-(U1-PA12_MISO(I2C{slash}SER2:0+)-Pad21)") (class "Default")
      (node (ref "U1") (pin "21") (pinfunction "PA12_MISO(I2C/SER2:0+)_21") (pintype "bidirectional"))
    )
    (net (code "57") (name "unconnected-(U1-PA13_38(I2C{slash}SER2:1+)-Pad22)") (class "Default")
      (node (ref "U1") (pin "22") (pinfunction "PA13_38(I2C/SER2:1+)_22") (pintype "bidirectional"))
    )
    (net (code "58") (name "unconnected-(U1-PA27_PIN_LED_TXL-Pad39)") (class "Default")
      (node (ref "U1") (pin "39") (pinfunction "PA27_PIN_LED_TXL_39") (pintype "bidirectional"))
    )
    (net (code "59") (name "unconnected-(U1-PA28-Pad41)") (class "Default")
      (node (ref "U1") (pin "41") (pinfunction "PA28_41") (pintype "bidirectional"))
    )
    (net (code "60") (name "unconnected-(U1-PB03_PIN_LED_RXL(AIN11{slash}SER5:1)-Pad48)") (class "Default")
      (node (ref "U1") (pin "48") (pinfunction "PB03_PIN_LED_RXL(AIN11/SER5:1)_48") (pintype "bidirectional"))
    )
    (net (code "61") (name "unconnected-(U1-PB10_MOSI(SER4:2+)-Pad19)") (class "Default")
      (node (ref "U1") (pin "19") (pinfunction "PB10_MOSI(SER4:2+)_19") (pintype "bidirectional"))
    )
    (net (code "62") (name "unconnected-(U1-PB11_SCK(SER4:3+)-Pad20)") (class "Default")
      (node (ref "U1") (pin "20") (pinfunction "PB11_SCK(SER4:3+)_20") (pintype "bidirectional"))
    )
    (net (code "63") (name "unconnected-(U1-PB22_30{slash}TX(SER5:2+)-Pad37)") (class "Default")
      (node (ref "U1") (pin "37") (pinfunction "PB22_30/TX(SER5:2+)_37") (pintype "bidirectional"))
    )
    (net (code "64") (name "unconnected-(U1-PB23_31{slash}RX(SER5:3+)-Pad38)") (class "Default")
      (node (ref "U1") (pin "38") (pinfunction "PB23_31/RX(SER5:3+)_38") (pintype "bidirectional"))
    )
  )
)
